# chassis.net
KiCad netlist of a schematic drawn in EAGLE
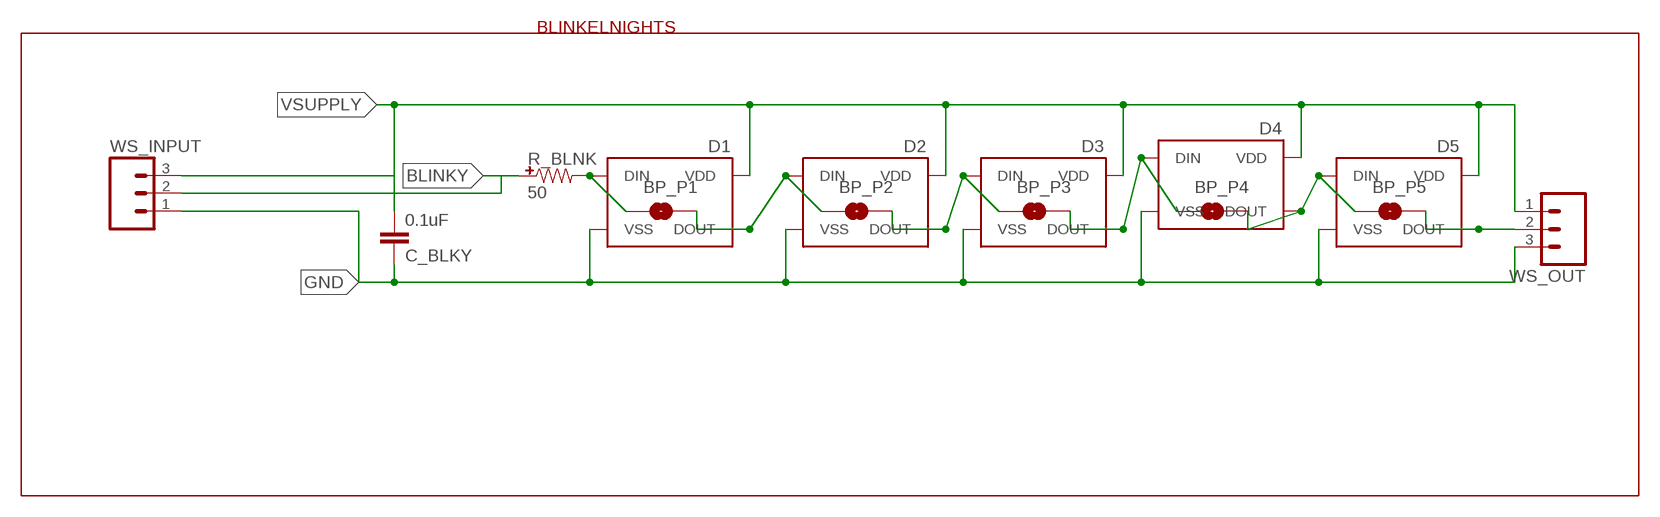
[diagram p0: schematic, sheet 1]

(export (version "E")
  (design (tool "Eeschema 10.0.6"))
  (components
    (comp (ref "BP_P1")
      (value "JUMPER-PAD-2-NOYES_SILK")
      (footprint "eagle-import:PAD-JUMPER-2-NO_YES_SILK")
      (libsource (lib "eagle-import") (part "JUMPER-PAD-2-NOYES_SILK"))
    )
    (comp (ref "BP_P2")
      (value "JUMPER-PAD-2-NOYES_SILK")
      (footprint "eagle-import:PAD-JUMPER-2-NO_YES_SILK")
      (libsource (lib "eagle-import") (part "JUMPER-PAD-2-NOYES_SILK"))
    )
    (comp (ref "BP_P3")
      (value "JUMPER-PAD-2-NOYES_SILK")
      (footprint "eagle-import:PAD-JUMPER-2-NO_YES_SILK")
      (libsource (lib "eagle-import") (part "JUMPER-PAD-2-NOYES_SILK"))
    )
    (comp (ref "BP_P4")
      (value "JUMPER-PAD-2-NOYES_SILK")
      (footprint "eagle-import:PAD-JUMPER-2-NO_YES_SILK")
      (libsource (lib "eagle-import") (part "JUMPER-PAD-2-NOYES_SILK"))
    )
    (comp (ref "BP_P5")
      (value "JUMPER-PAD-2-NOYES_SILK")
      (footprint "eagle-import:PAD-JUMPER-2-NO_YES_SILK")
      (libsource (lib "eagle-import") (part "JUMPER-PAD-2-NOYES_SILK"))
    )
    (comp (ref "C_BLKY")
      (value "0.1uF")
      (footprint "eagle-import:0402-0603-0805-UNIVERSAL")
      (libsource (lib "eagle-import") (part "CAPUNIVERSAL"))
    )
    (comp (ref "D1")
      (value "WS2812B")
      (footprint "eagle-import:WS2812B")
      (libsource (lib "eagle-import") (part "WS2812B"))
    )
    (comp (ref "D2")
      (value "WS2812B")
      (footprint "eagle-import:WS2812B")
      (libsource (lib "eagle-import") (part "WS2812B"))
    )
    (comp (ref "D3")
      (value "WS2812B")
      (footprint "eagle-import:WS2812B")
      (libsource (lib "eagle-import") (part "WS2812B"))
    )
    (comp (ref "D4")
      (value "WS2812B")
      (footprint "eagle-import:WS2812B")
      (libsource (lib "eagle-import") (part "WS2812B"))
    )
    (comp (ref "D5")
      (value "WS2812B")
      (footprint "eagle-import:WS2812B")
      (libsource (lib "eagle-import") (part "WS2812B"))
    )
    (comp (ref "R_BLNK")
      (value "50")
      (footprint "eagle-import:0402-0603-0805-UNIVERSAL")
      (libsource (lib "eagle-import") (part "RESISTORUNIVERSAL"))
    )
    (comp (ref "WS_INPUT")
      (value "M03LOCK")
      (footprint "eagle-import:1X03_LOCK")
      (libsource (lib "eagle-import") (part "M03LOCK"))
    )
    (comp (ref "WS_OUT")
      (value "M03LOCK")
      (footprint "eagle-import:1X03_LOCK")
      (libsource (lib "eagle-import") (part "M03LOCK"))
    )
  )
  (nets
    (net (code "1") (name "BLINKY") (class "Default")
      (node (ref "R_BLNK") (pin "-") (pinfunction "1_-") (pintype "passive"))
      (node (ref "WS_INPUT") (pin "2") (pinfunction "2_2") (pintype "passive"))
    )
    (net (code "2") (name "GND") (class "Default")
      (node (ref "C_BLKY") (pin "-") (pinfunction "1_-") (pintype "passive"))
      (node (ref "D1") (pin "3") (pinfunction "VSS_3") (pintype "power_in"))
      (node (ref "D2") (pin "3") (pinfunction "VSS_3") (pintype "power_in"))
      (node (ref "D3") (pin "3") (pinfunction "VSS_3") (pintype "power_in"))
      (node (ref "D4") (pin "3") (pinfunction "VSS_3") (pintype "power_in"))
      (node (ref "D5") (pin "3") (pinfunction "VSS_3") (pintype "power_in"))
      (node (ref "WS_INPUT") (pin "1") (pinfunction "1_1") (pintype "passive"))
      (node (ref "WS_OUT") (pin "3") (pinfunction "3_3") (pintype "passive"))
    )
    (net (code "3") (name "Net-(D1-DIN)") (class "Default")
      (node (ref "BP_P1") (pin "1") (pinfunction "1_1") (pintype "passive"))
      (node (ref "D1") (pin "4") (pinfunction "DIN_4") (pintype "input"))
      (node (ref "R_BLNK") (pin "+") (pinfunction "2_+") (pintype "passive"))
    )
    (net (code "4") (name "Net-(D1-DOUT)") (class "Default")
      (node (ref "BP_P1") (pin "2") (pinfunction "2_2") (pintype "passive"))
      (node (ref "BP_P2") (pin "1") (pinfunction "1_1") (pintype "passive"))
      (node (ref "D1") (pin "2") (pinfunction "DOUT_2") (pintype "output"))
      (node (ref "D2") (pin "4") (pinfunction "DIN_4") (pintype "input"))
    )
    (net (code "5") (name "Net-(D2-DOUT)") (class "Default")
      (node (ref "BP_P2") (pin "2") (pinfunction "2_2") (pintype "passive"))
      (node (ref "BP_P3") (pin "1") (pinfunction "1_1") (pintype "passive"))
      (node (ref "D2") (pin "2") (pinfunction "DOUT_2") (pintype "output"))
      (node (ref "D3") (pin "4") (pinfunction "DIN_4") (pintype "input"))
    )
    (net (code "6") (name "Net-(D3-DOUT)") (class "Default")
      (node (ref "BP_P3") (pin "2") (pinfunction "2_2") (pintype "passive"))
      (node (ref "BP_P4") (pin "1") (pinfunction "1_1") (pintype "passive"))
      (node (ref "D3") (pin "2") (pinfunction "DOUT_2") (pintype "output"))
      (node (ref "D4") (pin "4") (pinfunction "DIN_4") (pintype "input"))
    )
    (net (code "7") (name "Net-(D4-DOUT)") (class "Default")
      (node (ref "BP_P4") (pin "2") (pinfunction "2_2") (pintype "passive"))
      (node (ref "BP_P5") (pin "1") (pinfunction "1_1") (pintype "passive"))
      (node (ref "D4") (pin "2") (pinfunction "DOUT_2") (pintype "output"))
      (node (ref "D5") (pin "4") (pinfunction "DIN_4") (pintype "input"))
    )
    (net (code "8") (name "Net-(D5-DOUT)") (class "Default")
      (node (ref "BP_P5") (pin "2") (pinfunction "2_2") (pintype "passive"))
      (node (ref "D5") (pin "2") (pinfunction "DOUT_2") (pintype "output"))
      (node (ref "WS_OUT") (pin "2") (pinfunction "2_2") (pintype "passive"))
    )
    (net (code "9") (name "VSUPPLY") (class "Default")
      (node (ref "C_BLKY") (pin "+") (pinfunction "2_+") (pintype "passive"))
      (node (ref "D1") (pin "1") (pinfunction "VDD_1") (pintype "power_in"))
      (node (ref "D2") (pin "1") (pinfunction "VDD_1") (pintype "power_in"))
      (node (ref "D3") (pin "1") (pinfunction "VDD_1") (pintype "power_in"))
      (node (ref "D4") (pin "1") (pinfunction "VDD_1") (pintype "power_in"))
      (node (ref "D5") (pin "1") (pinfunction "VDD_1") (pintype "power_in"))
      (node (ref "WS_INPUT") (pin "3") (pinfunction "3_3") (pintype "passive"))
      (node (ref "WS_OUT") (pin "1") (pinfunction "1_1") (pintype "passive"))
    )
  )
)
